# 002-0081_Rev_-.net
KiCad netlist of a schematic drawn in Altium Designer
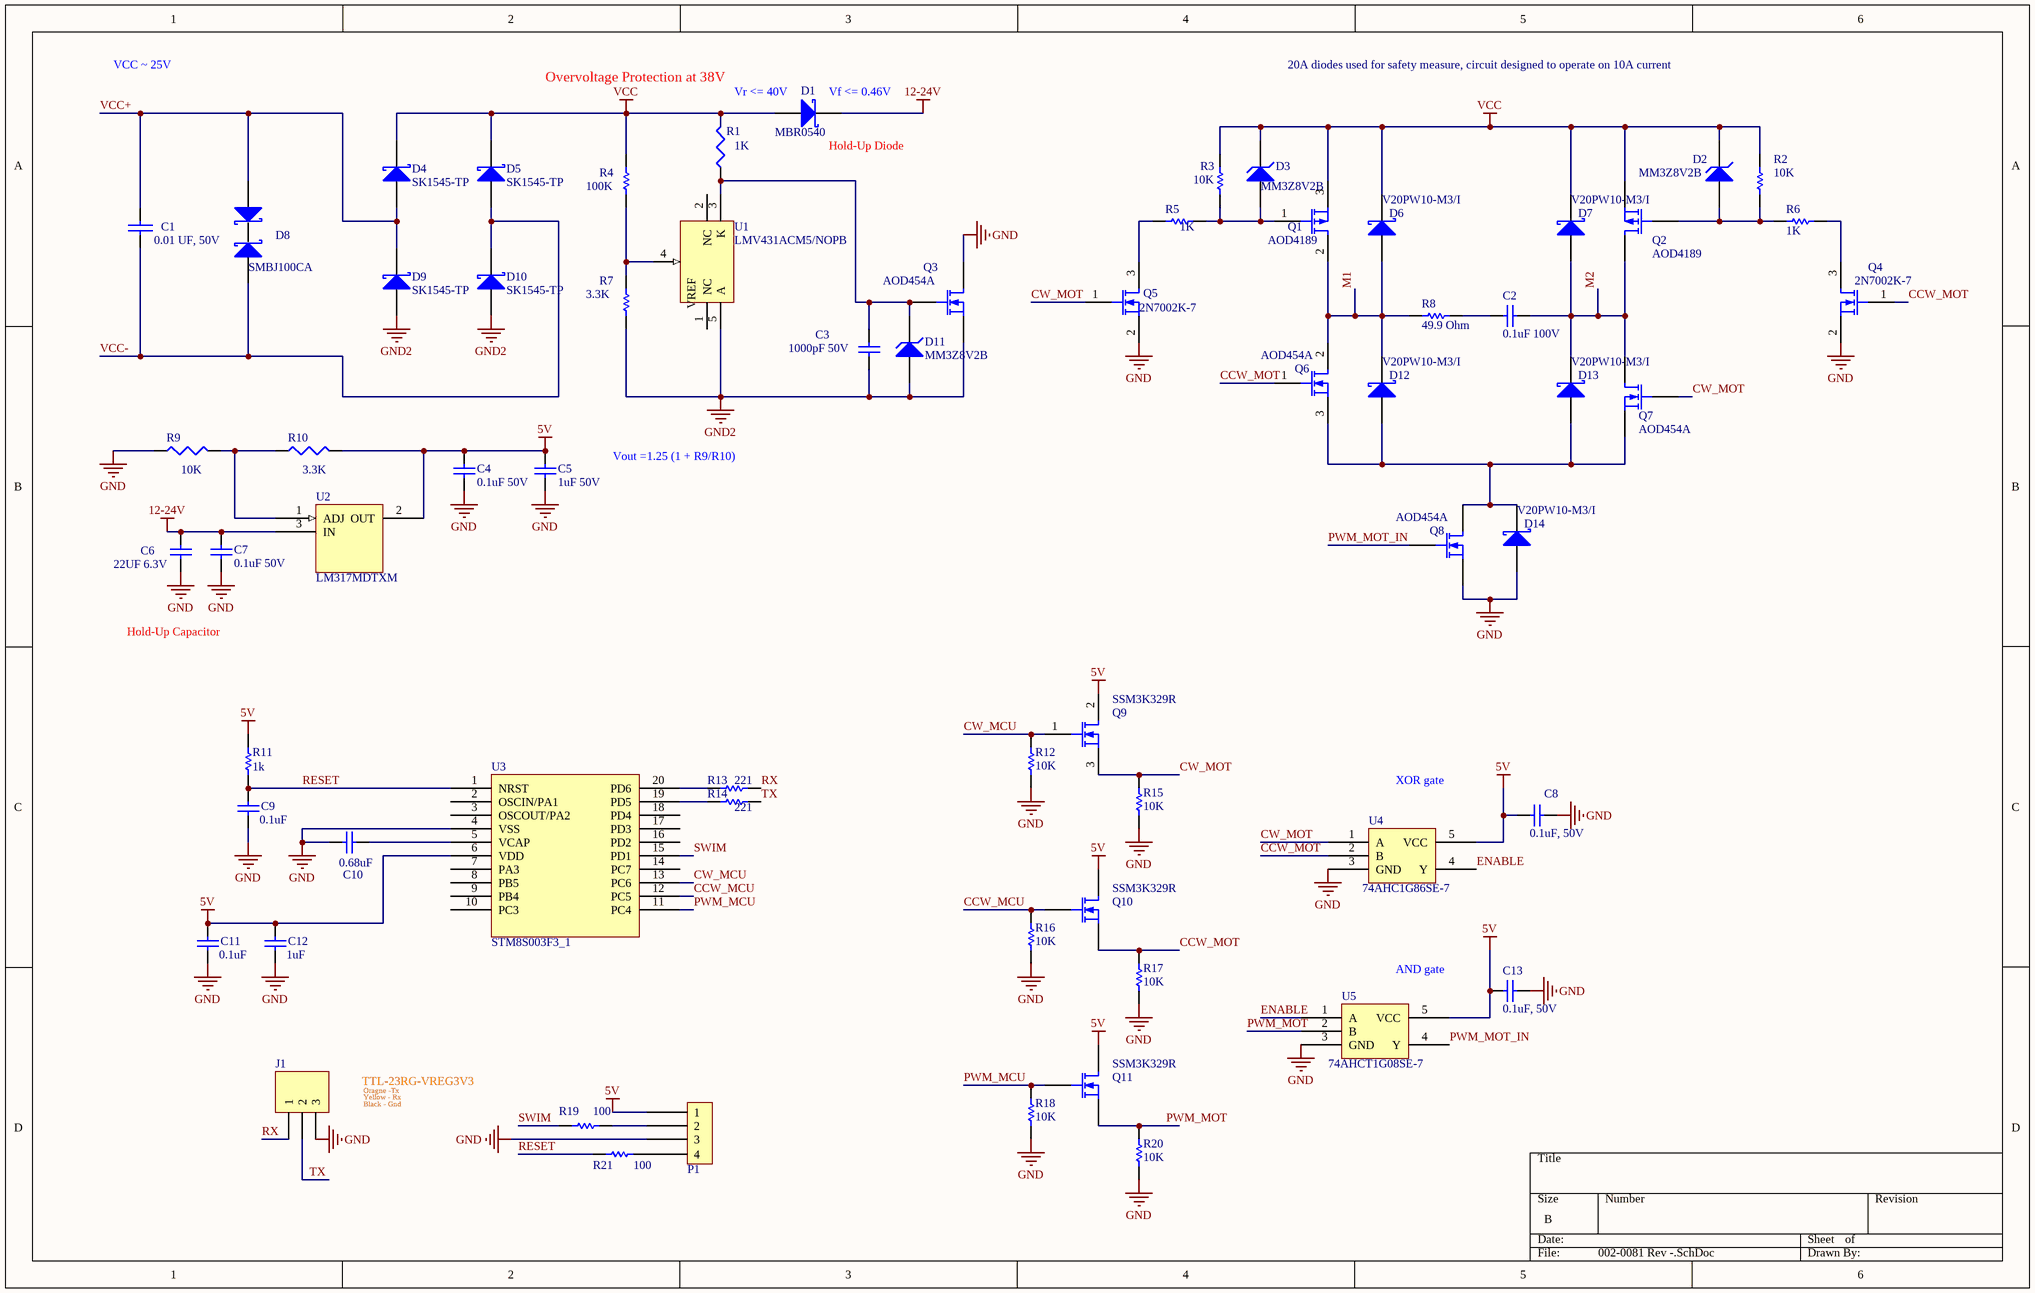
[diagram p0: 002-0081 Rev -.SchDoc]

(export (version "E")
  (design (tool "Eeschema 10.0.6"))
  (components
    (comp (ref "C1")
      (value "0.01 UF, 50V")
      (footprint "0603")
      (description "Cap Cer .01uf 50V 0603 RoHS")
      (fields
        (field (name "PEM PART NUMBER") "EE-1293")
        (field (name "MANUFACTURER") "Garrett Electronics Corporation")
      )
      (libsource (lib "*") (part "CAP"))
    )
    (comp (ref "C2")
      (value "0.1uF 100V")
      (footprint "RESC0805(2012)_N")
      (description "Cap Cer 0.1uF 100V 10% X7R 0805")
      (fields (field (name "PART NUMBER") "CL21B104KCFSFNE") (field (name "PEM PART NUMBER") "EE-1659"))
      (libsource (lib "Miscellaneous Devices") (part "Cap"))
    )
    (comp (ref "C3")
      (value "1000pF 50V")
      (footprint "0603")
      (description "CAP Cer, 0.1uF, 50V, 0603 X7R, 10%")
      (fields
        (field (name "MANUFACTURER PART NUMBER") "06035C104KAT2A")
        (field (name "PEM PART NUMBER") "EE-1343")
      )
      (libsource (lib "Miscellaneous Devices") (part "Cap"))
    )
    (comp (ref "C4")
      (value "0.1uF 50V")
      (footprint "0603")
      (description "CAP Cer, 0.1uF, 50V, 0603 X7R, 10%")
      (fields
        (field (name "MANUFACTURER PART NUMBER") "06035C104KAT2A")
        (field (name "PEM PART NUMBER") "EE-1425")
      )
      (libsource (lib "Miscellaneous Devices") (part "Cap"))
    )
    (comp (ref "C5")
      (value "1uF 50V")
      (footprint "0603")
      (description "CAP CER 1UF 50V 10% X5R 0603")
      (fields
        (field (name "MANUFACTURER PART NUMBER") "06035C104KAT2A")
        (field (name "PEM PART NUMBER") "EE-1708")
      )
      (libsource (lib "Miscellaneous Devices") (part "Cap"))
    )
    (comp (ref "C6")
      (value "22UF 6.3V")
      (footprint "0603")
      (description "CAP CER 22UF 6.3V X5R 0603")
      (fields
        (field (name "MANUFACTURER PART NUMBER") "06035C104KAT2A")
        (field (name "PEM PART NUMBER") "EE-1981")
      )
      (libsource (lib "Miscellaneous Devices") (part "Cap"))
    )
    (comp (ref "C7")
      (value "0.1uF 50V")
      (footprint "0603")
      (description "CAP Cer, 0.1uF, 50V, 0603 X7R, 10%")
      (fields
        (field (name "MANUFACTURER PART NUMBER") "06035C104KAT2A")
        (field (name "PEM PART NUMBER") "EE-1425")
      )
      (libsource (lib "Miscellaneous Devices") (part "Cap"))
    )
    (comp (ref "C8")
      (value "0.1uF, 50V")
      (footprint "0603")
      (description "CAP Cer, 0.1uF, 50V, 0603 X7R, 10%")
      (fields (field (name "PEM PART NUMBER") "EE-1425") (field (name "PART NUMBER") "06035C104KAT2A"))
      (libsource (lib "Miscellaneous Devices") (part "Cap"))
    )
    (comp (ref "C9")
      (value "0.1uF")
      (footprint "CAPC0402(1005)60_M")
      (description "Cap Cer 0.1uF 10V 10% X5R 0402")
      (fields (field (name "PART NUMBER") "LMK105BJ104KV-F") (field (name "PEM PART NUMBER") "EE-1661"))
      (libsource (lib "Miscellaneous Devices") (part "Cap"))
    )
    (comp (ref "C10")
      (value "0.68uF")
      (footprint "CAPC0402(1005)60_M")
      (description "Cap cer 0.68uF 6.3V 5% X6S 0402")
      (fields (field (name "PEM PART NUMBER") "EE-1673") (field (name "PART NUMBER") "CL05X684JQ5NNNC"))
      (libsource (lib "Miscellaneous Devices") (part "Cap"))
    )
    (comp (ref "C11")
      (value "0.1uF")
      (footprint "CAPC0402(1005)60_M")
      (description "Cap Cer 0.1uF 10V 10% X5R 0402")
      (fields (field (name "PART NUMBER") "LMK105BJ104KV-F") (field (name "PEM PART NUMBER") "EE-1661"))
      (libsource (lib "Miscellaneous Devices") (part "Cap"))
    )
    (comp (ref "C12")
      (value "1uF")
      (footprint "CAPC0402(1005)60_M")
      (description "Cap Cer 1uF 10V 10% X5R 0402")
      (fields (field (name "PART NUMBER") "C1005X5R1V105M050BC") (field (name "PEM PART NUMBER") "EE-1725"))
      (libsource (lib "Miscellaneous Devices") (part "Cap"))
    )
    (comp (ref "C13")
      (value "0.1uF, 50V")
      (footprint "0603")
      (description "Cap Cer 0.1uF 10V 10% X5R 0402")
      (fields (field (name "PEM PART NUMBER") "EE-1425") (field (name "PART NUMBER") "06035C104KAT2A"))
      (libsource (lib "Miscellaneous Devices") (part "Cap"))
    )
    (comp (ref "D1")
      (value "MBR0540")
      (footprint "SOD123/X.85")
      (description "Diode Schottky 40V 500ma SOD-123")
      (fields
        (field (name "MANUFACTURER PART NUMBER") "MBR0540-TP")
        (field (name "PEM PART NUMBER") "EE-1290")
      )
      (libsource (lib "") (part "D Schottky_1"))
    )
    (comp (ref "D2")
      (value "MM3Z8V2B")
      (footprint "SOD-323F")
      (description "DIODE ZENER 8.2V 200MW SOD323F")
      (fields (field (name "PEM PART NUMBER") "EE-1681"))
      (libsource (lib "Miscellaneous Devices") (part "D Zener"))
    )
    (comp (ref "D3")
      (value "MM3Z8V2B")
      (footprint "SOD-323F")
      (description "DIODE ZENER 8.2V 200MW SOD323F")
      (fields (field (name "PEM PART NUMBER") "EE-1681"))
      (libsource (lib "Miscellaneous Devices") (part "D Zener"))
    )
    (comp (ref "D4")
      (value "SK1545-TP")
      (footprint "SMC")
      (description "DIODE SCHOTTKY 45V 15A DO214AB")
      (fields (field (name "PEM PART NUMBER") "EE-2167"))
      (libsource (lib "Miscellaneous Devices") (part "D Schottky"))
    )
    (comp (ref "D5")
      (value "SK1545-TP")
      (footprint "SMC")
      (description "DIODE SCHOTTKY 45V 15A DO214AB")
      (fields (field (name "PEM PART NUMBER") "EE-2167"))
      (libsource (lib "Miscellaneous Devices") (part "D Schottky"))
    )
    (comp (ref "D6")
      (value "V20PW10-M3/I")
      (footprint "DPAK (TO-252-3)")
      (description "DIODE SCHOTTKY 100V 20A SLIMDPAK")
      (fields (field (name "PEM PART NUMBER") "EE-2166"))
      (libsource (lib "Miscellaneous Devices") (part "D Schottky"))
    )
    (comp (ref "D7")
      (value "V20PW10-M3/I")
      (footprint "DPAK (TO-252-3)")
      (description "DIODE SCHOTTKY 100V 20A SLIMDPAK")
      (fields (field (name "PEM PART NUMBER") "EE-2166"))
      (libsource (lib "Miscellaneous Devices") (part "D Schottky"))
    )
    (comp (ref "D8")
      (value "TVS DIODE 28VWM 45.4VC SMB")
      (footprint "SMB - Bidirection")
      (description "TVS DIODE 100VWM 162VC DO214AA")
      (fields
        (field (name "PART NUMBER") "SMBJ100CA")
        (field (name "MANUFACTURER") "ON Semiconductor")
        (field (name "PEM PART NUMBER") "EE-1946")
      )
      (libsource (lib "002-0017 Rev H") (part "Dual Zener"))
    )
    (comp (ref "D9")
      (value "SK1545-TP")
      (footprint "SMC")
      (description "DIODE SCHOTTKY 45V 15A DO214AB")
      (fields (field (name "PEM PART NUMBER") "EE-2167"))
      (libsource (lib "Miscellaneous Devices") (part "D Schottky"))
    )
    (comp (ref "D10")
      (value "SK1545-TP")
      (footprint "SMC")
      (description "DIODE SCHOTTKY 45V 15A DO214AB")
      (fields (field (name "PEM PART NUMBER") "EE-2167"))
      (libsource (lib "Miscellaneous Devices") (part "D Schottky"))
    )
    (comp (ref "D11")
      (value "MM3Z8V2B")
      (footprint "SOD-323F")
      (description "DIODE ZENER 8.2V 200MW SOD323F")
      (fields (field (name "PEM PART NUMBER") "EE-1681"))
      (libsource (lib "Miscellaneous Devices") (part "D Zener"))
    )
    (comp (ref "D12")
      (value "V20PW10-M3/I")
      (footprint "DPAK (TO-252-3)")
      (description "DIODE SCHOTTKY 100V 20A SLIMDPAK")
      (fields (field (name "PEM PART NUMBER") "EE-2166"))
      (libsource (lib "Miscellaneous Devices") (part "D Schottky"))
    )
    (comp (ref "D13")
      (value "V20PW10-M3/I")
      (footprint "DPAK (TO-252-3)")
      (description "DIODE SCHOTTKY 100V 20A SLIMDPAK")
      (fields (field (name "PEM PART NUMBER") "EE-2166"))
      (libsource (lib "Miscellaneous Devices") (part "D Schottky"))
    )
    (comp (ref "D14")
      (value "V20PW10-M3/I")
      (footprint "DPAK (TO-252-3)")
      (description "DIODE SCHOTTKY 100V 20A SLIMDPAK")
      (fields (field (name "PEM PART NUMBER") "EE-2166"))
      (libsource (lib "Miscellaneous Devices") (part "D Schottky"))
    )
    (comp (ref "J1")
      (value "RS232 Conn")
      (footprint "SCON3/.10")
      (description "CONN HDR VERT 3POS .100 TIN")
      (fields
        (field (name "PEM PART NUMBER") "EE-1116")
        (field (name "MANUFACTURER") "Phoenix Contact")
        (field (name "PUBLISHER") "Altium Limited")
      )
      (libsource (lib "Miscellaneous Connectors") (part "Header 3"))
    )
    (comp (ref "P1")
      (value "4 Pin Connector")
      (footprint "4 PIN IN-LINE")
      (fields
        (field (name "PEM PART NUMBER") "EE-1855")
        (field (name "PART NUMBER") "GRPB501VWVN-RC")
        (field (name "MANUFACTURER") "Sullins Connector Solutions")
      )
      (libsource (lib "002 - 0053 Rev A") (part "4 Pin Connector"))
    )
    (comp (ref "Q1")
      (value "AOD4189")
      (footprint "DPAK (TO-252-3)")
      (description "MOSFET P-CH 40V 40A TO252 DPAK")
      (fields (field (name "PEM PART NUMBER") "EE-1879"))
      (libsource (lib "") (part "MOSFET-P_1"))
    )
    (comp (ref "Q2")
      (value "AOD4189")
      (footprint "DPAK (TO-252-3)")
      (description "MOSFET P-CH 40V 40A TO252 DPAK")
      (fields (field (name "PEM PART NUMBER") "EE-1879"))
      (libsource (lib "Miscellaneous Devices") (part "MOSFET-P"))
    )
    (comp (ref "Q3")
      (value "AOD454A")
      (footprint "DPAK (TO-252-3)")
      (description "MOSFET N-CH 250V 16A D-PAK")
      (fields (field (name "PEM PART NUMBER") "EE-1898"))
      (libsource (lib "") (part "MOSFET-N_2"))
    )
    (comp (ref "Q4")
      (value "2N7002K-7")
      (footprint "SOT-23-3")
      (description "MOSFET N-CH 60V 0.38A SOT23-3")
      (fields (field (name "PEM PART NUMBER") "EE-2053"))
      (libsource (lib "") (part "MOSFET-N_1"))
    )
    (comp (ref "Q5")
      (value "2N7002K-7")
      (footprint "SOT-23-3")
      (description "MOSFET N-CH 60V 0.38A SOT23-3")
      (fields (field (name "PEM PART NUMBER") "EE-2053"))
      (libsource (lib "") (part "MOSFET-N_1"))
    )
    (comp (ref "Q6")
      (value "AOD454A")
      (footprint "DPAK (TO-252-3)")
      (description "MOSFET N-CH 40V 20A TO252")
      (fields
        (field (name "MANUFACTURER") "Alpha & Omega Semiconductor Inc.")
        (field (name "PEM PART NUMBER") "EE-1898")
      )
      (libsource (lib "Miscellaneous Devices") (part "MOSFET-N"))
    )
    (comp (ref "Q7")
      (value "AOD454A")
      (footprint "DPAK (TO-252-3)")
      (description "MOSFET N-CH 40V 20A TO252")
      (fields
        (field (name "MANUFACTURER") "Alpha & Omega Semiconductor Inc.")
        (field (name "PEM PART NUMBER") "EE-1898")
      )
      (libsource (lib "") (part "MOSFET-N_2"))
    )
    (comp (ref "Q8")
      (value "AOD454A")
      (footprint "DPAK (TO-252-3)")
      (description "MOSFET N-CH 40V 20A TO252")
      (fields
        (field (name "MANUFACTURER") "Alpha & Omega Semiconductor Inc.")
        (field (name "PEM PART NUMBER") "EE-1898")
      )
      (libsource (lib "") (part "MOSFET-N_2"))
    )
    (comp (ref "Q9")
      (value "SSM3K329R")
      (footprint "SOT-23F")
      (description "N-Channel 30V 3.5A (Ta) 1W (Ta) Surface Mount SOT-23F")
      (fields
        (field (name "MANUFACTURER") "Alpha & Omega Semiconductor Inc.")
        (field (name "PEM PART NUMBER") "EE-1830")
      )
      (libsource (lib "Miscellaneous Devices") (part "MOSFET-N"))
    )
    (comp (ref "Q10")
      (value "SSM3K329R")
      (footprint "SOT-23F")
      (description "N-Channel 30V 3.5A (Ta) 1W (Ta) Surface Mount SOT-23F")
      (fields
        (field (name "MANUFACTURER") "Alpha & Omega Semiconductor Inc.")
        (field (name "PEM PART NUMBER") "EE-1830")
      )
      (libsource (lib "") (part "MOSFET-N_2"))
    )
    (comp (ref "Q11")
      (value "SSM3K329R")
      (footprint "SOT-23F")
      (description "N-Channel 30V 3.5A (Ta) 1W (Ta) Surface Mount SOT-23F")
      (fields
        (field (name "PART NUMBER") "AOD454A")
        (field (name "MANUFACTURER") "Alpha & Omega Semiconductor Inc.")
      )
      (libsource (lib "") (part "MOSFET-N_2"))
    )
    (comp (ref "R1")
      (value "1K")
      (footprint "002-0081 Rev -:RESC0603(1608)_M")
      (description "RES SMD 1K OHM 1% 1/10W 0603")
      (fields
        (field (name "PEM PART NUMBER") "EE-2066")
        (field (name "Comment") "Res3")
        (field (name "PUBLISHER") "Altium Limited")
      )
      (libsource (lib "Miscellaneous Devices") (part "Res3"))
    )
    (comp (ref "R2")
      (value "10K")
      (footprint "RESC0603(1608)_M")
      (description "Res 10K 0603 1% 1/10W RoHS")
      (fields (field (name "PART NUMBER") "RK73H1JTTD1002F") (field (name "PEM PART NUMBER") "EE-1296"))
      (libsource (lib "Miscellaneous Devices") (part "Res1"))
    )
    (comp (ref "R3")
      (value "10K")
      (footprint "RESC0603(1608)_M")
      (description "Res 10K 0603 1% 1/10W RoHS")
      (fields (field (name "PART NUMBER") "RK73H1JTTD1002F") (field (name "PEM PART NUMBER") "EE-1296"))
      (libsource (lib "Miscellaneous Devices") (part "Res1"))
    )
    (comp (ref "R4")
      (value "100K")
      (footprint "RESC0603(1608)_M")
      (description "Res 100K 0603 1% 1/10W RoHS")
      (fields (field (name "PART NUMBER") "RK73H1JTTD1002F") (field (name "PEM PART NUMBER") "EE-1295"))
      (libsource (lib "Miscellaneous Devices") (part "Res1"))
    )
    (comp (ref "R5")
      (value "1K")
      (footprint "RESC0603(1608)_M")
      (description "Res 1.0K 0603 1% 1/10W RoHS")
      (fields
        (field (name "MANUFACTURER PART NUMBER") "CRCW06031K00FKEA")
        (field (name "PEM PART NUMBER") "EE-1297")
      )
      (libsource (lib "Miscellaneous Devices") (part "Res1"))
    )
    (comp (ref "R6")
      (value "1K")
      (footprint "RESC0603(1608)_M")
      (description "Res 1.0K 0603 1% 1/10W RoHS")
      (fields
        (field (name "MANUFACTURER PART NUMBER") "CRCW06031K00FKEA")
        (field (name "PEM PART NUMBER") "EE-1297")
      )
      (libsource (lib "Miscellaneous Devices") (part "Res1"))
    )
    (comp (ref "R7")
      (value "3.3K")
      (footprint "RESC0603(1608)_M")
      (description "RES 23.7K OHM 1/10W 1% 0603 SMD")
      (fields (field (name "PART NUMBER") "MCR03ERTF3301") (field (name "PEM PART NUMBER") "EE-1730"))
      (libsource (lib "Miscellaneous Devices") (part "Res1"))
    )
    (comp (ref "R8")
      (value "49.9 Ohm")
      (footprint "RESC0805(2012)_N")
      (description "Res 49.9R 0805 1% 1/8W")
      (fields (field (name "PEM PART NUMBER") "EE-1238") (field (name "PART NUMBER") "9C08052A49R9FKHFT"))
      (libsource (lib "Miscellaneous Devices") (part "Res1"))
    )
    (comp (ref "R9")
      (value "10K")
      (footprint "J1-0603")
      (description "Res 10K 0603 1% 1/10W RoHS")
      (fields (field (name "PEM PART NUMBER") "EE-1296") (field (name "PART NUMBER") "RK73H1JTTD1002F"))
      (libsource (lib "Miscellaneous Devices") (part "Res3"))
    )
    (comp (ref "R10")
      (value "3.3K")
      (footprint "J1-0603")
      (description "Res 3.3K 0603 1% 1/8W RoHS")
      (fields (field (name "PEM PART NUMBER") "EE-1730") (field (name "PART NUMBER") "MCR03ERTF3301"))
      (libsource (lib "Miscellaneous Devices") (part "Res3"))
    )
    (comp (ref "R11")
      (value "1k")
      (footprint "RESC0402(1005)_N")
      (description "Res 1K 0402 1% 1/16W RoHS")
      (fields (field (name "PEM PART NUMBER") "EE-1581") (field (name "PART NUMBER") "CRCW04021K00FKED"))
      (libsource (lib "Miscellaneous Devices") (part "Res1"))
    )
    (comp (ref "R12")
      (value "10K")
      (footprint "RESC0603(1608)_M")
      (description "Res 10K 0603 1% 1/10W RoHS")
      (fields (field (name "PART NUMBER") "RK73H1JTTD1002F") (field (name "PEM PART NUMBER") "EE-1296"))
      (libsource (lib "Miscellaneous Devices") (part "Res1"))
    )
    (comp (ref "R13")
      (value "221")
      (footprint "RESC0402(1005)_N")
      (description "RES SMD 221 OHM 1% 1/16W 0402")
      (fields (field (name "PART NUMBER") "RC1005F2210CS") (field (name "PEM PART NUMBER") "EE-1798"))
      (libsource (lib "Miscellaneous Devices") (part "Res1"))
    )
    (comp (ref "R14")
      (value "221")
      (footprint "RESC0402(1005)_N")
      (description "Res 1K 0603 1% 1/10W RoHS")
      (fields (field (name "PART NUMBER") "RC1005F2210CS") (field (name "PEM PART NUMBER") "EE-1798"))
      (libsource (lib "Miscellaneous Devices") (part "Res1"))
    )
    (comp (ref "R15")
      (value "10K")
      (footprint "RESC0603(1608)_M")
      (description "Res 10K 0603 1% 1/10W RoHS")
      (fields (field (name "PART NUMBER") "RK73H1JTTD1002F") (field (name "PEM PART NUMBER") "EE-1296"))
      (libsource (lib "Miscellaneous Devices") (part "Res1"))
    )
    (comp (ref "R16")
      (value "10K")
      (footprint "RESC0603(1608)_M")
      (description "Res 10K 0603 1% 1/10W RoHS")
      (fields (field (name "PART NUMBER") "RK73H1JTTD1002F") (field (name "PEM PART NUMBER") "EE-1296"))
      (libsource (lib "Miscellaneous Devices") (part "Res1"))
    )
    (comp (ref "R17")
      (value "10K")
      (footprint "RESC0603(1608)_M")
      (description "Res 10K 0603 1% 1/10W RoHS")
      (fields (field (name "PART NUMBER") "RK73H1JTTD1002F") (field (name "PEM PART NUMBER") "EE-1296"))
      (libsource (lib "Miscellaneous Devices") (part "Res1"))
    )
    (comp (ref "R18")
      (value "10K")
      (footprint "RESC0603(1608)_M")
      (description "Res 10K 0603 1% 1/10W RoHS")
      (fields (field (name "PART NUMBER") "RK73H1JTTD1002F") (field (name "PEM PART NUMBER") "EE-1296"))
      (libsource (lib "Miscellaneous Devices") (part "Res1"))
    )
    (comp (ref "R19")
      (value "100")
      (footprint "RESC0402(1005)_N")
      (description "Res 100R 0402 1% 1/16W RoHs")
      (fields (field (name "PEM PART NUMBER") "EE-1588") (field (name "PART NUMBER") "RC0402FR-07100RL"))
      (libsource (lib "Miscellaneous Devices") (part "Res1"))
    )
    (comp (ref "R20")
      (value "10K")
      (footprint "RESC0603(1608)_M")
      (description "Res 10K 0603 1% 1/10W RoHS")
      (fields (field (name "PART NUMBER") "RK73H1JTTD1002F") (field (name "PEM PART NUMBER") "EE-1296"))
      (libsource (lib "Miscellaneous Devices") (part "Res1"))
    )
    (comp (ref "R21")
      (value "100")
      (footprint "RESC0402(1005)_N")
      (description "Res 100R 0402 1% 1/16W RoHs")
      (fields (field (name "PEM PART NUMBER") "EE-1588") (field (name "PART NUMBER") "RC0402FR-07100RL"))
      (libsource (lib "Miscellaneous Devices") (part "Res1"))
    )
    (comp (ref "U1")
      (value "LMV431ACM5/NOPB")
      (footprint "DBV005")
      (description "IC VREF SHUNT ADJ SOT23-5")
      (fields (field (name "PEM PART NUMBER") "EE-1900"))
      (libsource (lib "TI Power Mgt Voltage Regulator") (part "TL431IDBVR"))
    )
    (comp (ref "U2")
      (value "LM317MDTXM")
      (footprint "DPAK (TO-252-3)")
      (description "SMT, IC, Adjust Voltage Reg, 0.5A, 3TERM, TO-252, 40V diff max")
      (fields
        (field (name "PEM PART NUMBER") "EE-1248")
        (field (name "MANUFACTURER") "Fairchild Semiconductor")
      )
      (libsource (lib "*") (part "LM317D2T(3)"))
    )
    (comp (ref "U3")
      (value "STM8S003F3_1")
      (footprint "UFQFPN20_V")
      (description "MCU 8BIT 8KB 16MHZ 20-UFQFPN")
      (fields (field (name "PEM PART NUMBER") "EE-1655") (field (name "PART NUMBER") "STM8S003F3U6TR"))
      (libsource (lib "SlowActuator") (part "STM8S003F3_1"))
    )
    (comp (ref "U4")
      (value "74AHC1G86SE-7")
      (footprint "SOT-353")
      (description "IC GATE XOR 1CH 2-INP SOT353")
      (fields (field (name "PEM PART NUMBER") "EE-2165") (field (name "MANUFACTURER") "Diodes Incorporated"))
      (libsource (lib "002-0066 Rev -") (part "NC7SZ08"))
    )
    (comp (ref "U5")
      (value "74AHCT1G08SE-7")
      (footprint "SOT-353")
      (description "IC GATE AND 1CH 2-INP SOT-353")
      (fields (field (name "PEM PART NUMBER") "EE-1801") (field (name "MANUFACTURER") "Diodes Incorporated"))
      (libsource (lib "002-0066 Rev -") (part "NC7SZ08"))
    )
  )
  (nets
    (net (code "1") (name "/CCW_MCU") (class "Default")
      (node (ref "Q10") (pin "1") (pinfunction "G_1") (pintype "passive"))
      (node (ref "R16") (pin "1") (pinfunction "1_1") (pintype "passive"))
      (node (ref "U3") (pin "12") (pinfunction "PC5_12") (pintype "passive"))
    )
    (net (code "2") (name "/CCW_MOT") (class "Default")
      (node (ref "Q10") (pin "3") (pinfunction "S_3") (pintype "passive"))
      (node (ref "Q4") (pin "1") (pinfunction "G_1") (pintype "passive"))
      (node (ref "Q6") (pin "1") (pinfunction "G_1") (pintype "passive"))
      (node (ref "R17") (pin "1") (pinfunction "1_1") (pintype "passive"))
      (node (ref "U4") (pin "2") (pinfunction "B_2") (pintype "passive"))
    )
    (net (code "3") (name "/CW_MCU") (class "Default")
      (node (ref "Q9") (pin "1") (pinfunction "G_1") (pintype "passive"))
      (node (ref "R12") (pin "1") (pinfunction "1_1") (pintype "passive"))
      (node (ref "U3") (pin "13") (pinfunction "PC6_13") (pintype "passive"))
    )
    (net (code "4") (name "/CW_MOT") (class "Default")
      (node (ref "Q5") (pin "1") (pinfunction "G_1") (pintype "passive"))
      (node (ref "Q7") (pin "1") (pinfunction "G_1") (pintype "passive"))
      (node (ref "Q9") (pin "3") (pinfunction "S_3") (pintype "passive"))
      (node (ref "R15") (pin "1") (pinfunction "1_1") (pintype "passive"))
      (node (ref "U4") (pin "1") (pinfunction "A_1") (pintype "passive"))
    )
    (net (code "5") (name "/ENABLE") (class "Default")
      (node (ref "U4") (pin "4") (pinfunction "Y_4") (pintype "passive"))
      (node (ref "U5") (pin "1") (pinfunction "A_1") (pintype "passive"))
    )
    (net (code "6") (name "/M1") (class "Default")
      (node (ref "D12") (pin "2") (pinfunction "K_2") (pintype "passive"))
      (node (ref "D6") (pin "1") (pinfunction "A_1") (pintype "passive"))
      (node (ref "Q1") (pin "2") (pinfunction "D_2") (pintype "passive"))
      (node (ref "Q6") (pin "2") (pinfunction "D_2") (pintype "passive"))
      (node (ref "R8") (pin "2") (pinfunction "2_2") (pintype "passive"))
    )
    (net (code "7") (name "/M2") (class "Default")
      (node (ref "C2") (pin "1") (pinfunction "1_1") (pintype "passive"))
      (node (ref "D13") (pin "2") (pinfunction "K_2") (pintype "passive"))
      (node (ref "D7") (pin "1") (pinfunction "A_1") (pintype "passive"))
      (node (ref "Q2") (pin "2") (pinfunction "D_2") (pintype "passive"))
      (node (ref "Q7") (pin "2") (pinfunction "D_2") (pintype "passive"))
    )
    (net (code "8") (name "/PWM_MCU") (class "Default")
      (node (ref "Q11") (pin "1") (pinfunction "G_1") (pintype "passive"))
      (node (ref "R18") (pin "1") (pinfunction "1_1") (pintype "passive"))
      (node (ref "U3") (pin "11") (pinfunction "PC4_11") (pintype "passive"))
    )
    (net (code "9") (name "/PWM_MOT") (class "Default")
      (node (ref "Q11") (pin "3") (pinfunction "S_3") (pintype "passive"))
      (node (ref "R20") (pin "1") (pinfunction "1_1") (pintype "passive"))
      (node (ref "U5") (pin "2") (pinfunction "B_2") (pintype "passive"))
    )
    (net (code "10") (name "/PWM_MOT_IN") (class "Default")
      (node (ref "Q8") (pin "1") (pinfunction "G_1") (pintype "passive"))
      (node (ref "U5") (pin "4") (pinfunction "Y_4") (pintype "passive"))
    )
    (net (code "11") (name "/RESET") (class "Default")
      (node (ref "C9") (pin "2") (pinfunction "2_2") (pintype "passive"))
      (node (ref "R11") (pin "1") (pinfunction "1_1") (pintype "passive"))
      (node (ref "R21") (pin "1") (pinfunction "1_1") (pintype "passive"))
      (node (ref "U3") (pin "1") (pinfunction "NRST_1") (pintype "passive"))
    )
    (net (code "12") (name "/RX") (class "Default")
      (node (ref "J1") (pin "1") (pinfunction "1_1") (pintype "passive"))
      (node (ref "R13") (pin "2") (pinfunction "2_2") (pintype "passive"))
    )
    (net (code "13") (name "/SWIM") (class "Default")
      (node (ref "R19") (pin "1") (pinfunction "1_1") (pintype "passive"))
      (node (ref "U3") (pin "15") (pinfunction "PD1_15") (pintype "passive"))
    )
    (net (code "14") (name "/TX") (class "Default")
      (node (ref "J1") (pin "2") (pinfunction "2_2") (pintype "passive"))
      (node (ref "R14") (pin "2") (pinfunction "2_2") (pintype "passive"))
    )
    (net (code "15") (name "/VCC+") (class "Default")
      (node (ref "C1") (pin "1") (pinfunction "1_1") (pintype "passive"))
      (node (ref "D4") (pin "1") (pinfunction "A_1") (pintype "passive"))
      (node (ref "D8") (pin "2") (pinfunction "2_2") (pintype "passive"))
      (node (ref "D9") (pin "2") (pinfunction "K_2") (pintype "passive"))
    )
    (net (code "16") (name "/VCC-") (class "Default")
      (node (ref "C1") (pin "2") (pinfunction "2_2") (pintype "passive"))
      (node (ref "D10") (pin "2") (pinfunction "K_2") (pintype "passive"))
      (node (ref "D5") (pin "1") (pinfunction "A_1") (pintype "passive"))
      (node (ref "D8") (pin "1") (pinfunction "1_1") (pintype "passive"))
    )
    (net (code "17") (name "5V") (class "Default")
      (node (ref "C11") (pin "2") (pinfunction "2_2") (pintype "passive"))
      (node (ref "C12") (pin "2") (pinfunction "2_2") (pintype "passive"))
      (node (ref "C13") (pin "2") (pinfunction "2_2") (pintype "passive"))
      (node (ref "C4") (pin "2") (pinfunction "2_2") (pintype "passive"))
      (node (ref "C5") (pin "2") (pinfunction "2_2") (pintype "passive"))
      (node (ref "C8") (pin "2") (pinfunction "2_2") (pintype "passive"))
      (node (ref "P1") (pin "1") (pinfunction "1_1") (pintype "passive"))
      (node (ref "Q10") (pin "2") (pinfunction "D_2") (pintype "passive"))
      (node (ref "Q11") (pin "2") (pinfunction "D_2") (pintype "passive"))
      (node (ref "Q9") (pin "2") (pinfunction "D_2") (pintype "passive"))
      (node (ref "R10") (pin "2") (pinfunction "2_2") (pintype "passive"))
      (node (ref "R11") (pin "2") (pinfunction "2_2") (pintype "passive"))
      (node (ref "U2") (pin "2") (pinfunction "OUT_2") (pintype "power_in"))
      (node (ref "U3") (pin "6") (pinfunction "VDD_6") (pintype "passive"))
      (node (ref "U4") (pin "5") (pinfunction "VCC_5") (pintype "passive"))
      (node (ref "U5") (pin "5") (pinfunction "VCC_5") (pintype "passive"))
    )
    (net (code "18") (name "12-24V") (class "Default")
      (node (ref "C6") (pin "2") (pinfunction "2_2") (pintype "passive"))
      (node (ref "C7") (pin "2") (pinfunction "2_2") (pintype "passive"))
      (node (ref "D1") (pin "1") (pinfunction "K_1") (pintype "passive"))
      (node (ref "U2") (pin "3") (pinfunction "IN_3") (pintype "power_in"))
    )
    (net (code "19") (name "GND") (class "Default")
      (node (ref "C10") (pin "1") (pinfunction "1_1") (pintype "passive"))
      (node (ref "C11") (pin "1") (pinfunction "1_1") (pintype "passive"))
      (node (ref "C12") (pin "1") (pinfunction "1_1") (pintype "passive"))
      (node (ref "C13") (pin "1") (pinfunction "1_1") (pintype "passive"))
      (node (ref "C4") (pin "1") (pinfunction "1_1") (pintype "passive"))
      (node (ref "C5") (pin "1") (pinfunction "1_1") (pintype "passive"))
      (node (ref "C6") (pin "1") (pinfunction "1_1") (pintype "passive"))
      (node (ref "C7") (pin "1") (pinfunction "1_1") (pintype "passive"))
      (node (ref "C8") (pin "1") (pinfunction "1_1") (pintype "passive"))
      (node (ref "C9") (pin "1") (pinfunction "1_1") (pintype "passive"))
      (node (ref "D14") (pin "1") (pinfunction "A_1") (pintype "passive"))
      (node (ref "J1") (pin "3") (pinfunction "3_3") (pintype "passive"))
      (node (ref "P1") (pin "3") (pinfunction "3_3") (pintype "passive"))
      (node (ref "Q3") (pin "2") (pinfunction "D_2") (pintype "passive"))
      (node (ref "Q4") (pin "2") (pinfunction "S_2") (pintype "passive"))
      (node (ref "Q5") (pin "2") (pinfunction "S_2") (pintype "passive"))
      (node (ref "Q8") (pin "3") (pinfunction "S_3") (pintype "passive"))
      (node (ref "R12") (pin "2") (pinfunction "2_2") (pintype "passive"))
      (node (ref "R15") (pin "2") (pinfunction "2_2") (pintype "passive"))
      (node (ref "R16") (pin "2") (pinfunction "2_2") (pintype "passive"))
      (node (ref "R17") (pin "2") (pinfunction "2_2") (pintype "passive"))
      (node (ref "R18") (pin "2") (pinfunction "2_2") (pintype "passive"))
      (node (ref "R20") (pin "2") (pinfunction "2_2") (pintype "passive"))
      (node (ref "R9") (pin "1") (pinfunction "1_1") (pintype "passive"))
      (node (ref "U3") (pin "4") (pinfunction "VSS_4") (pintype "passive"))
      (node (ref "U4") (pin "3") (pinfunction "GND_3") (pintype "passive"))
      (node (ref "U5") (pin "3") (pinfunction "GND_3") (pintype "passive"))
    )
    (net (code "20") (name "GND2") (class "Default")
      (node (ref "C3") (pin "1") (pinfunction "1_1") (pintype "passive"))
      (node (ref "D10") (pin "1") (pinfunction "A_1") (pintype "passive"))
      (node (ref "D11") (pin "1") (pinfunction "A_1") (pintype "passive"))
      (node (ref "D9") (pin "1") (pinfunction "A_1") (pintype "passive"))
      (node (ref "Q3") (pin "3") (pinfunction "S_3") (pintype "passive"))
      (node (ref "R7") (pin "2") (pinfunction "2_2") (pintype "passive"))
      (node (ref "U1") (pin "5") (pinfunction "A_5") (pintype "power_in"))
    )
    (net (code "21") (name "Net-(C2-Pad2)") (class "Default")
      (node (ref "C2") (pin "2") (pinfunction "2_2") (pintype "passive"))
      (node (ref "R8") (pin "1") (pinfunction "1_1") (pintype "passive"))
    )
    (net (code "22") (name "Net-(D2-A)") (class "Default")
      (node (ref "D2") (pin "1") (pinfunction "A_1") (pintype "passive"))
      (node (ref "Q2") (pin "1") (pinfunction "G_1") (pintype "passive"))
      (node (ref "R2") (pin "2") (pinfunction "2_2") (pintype "passive"))
      (node (ref "R6") (pin "1") (pinfunction "1_1") (pintype "passive"))
    )
    (net (code "23") (name "Net-(D3-A)") (class "Default")
      (node (ref "D3") (pin "1") (pinfunction "A_1") (pintype "passive"))
      (node (ref "Q1") (pin "1") (pinfunction "G_1") (pintype "passive"))
      (node (ref "R3") (pin "2") (pinfunction "2_2") (pintype "passive"))
      (node (ref "R5") (pin "2") (pinfunction "2_2") (pintype "passive"))
    )
    (net (code "24") (name "Net-(D11-K)") (class "Default")
      (node (ref "C3") (pin "2") (pinfunction "2_2") (pintype "passive"))
      (node (ref "D11") (pin "2") (pinfunction "K_2") (pintype "passive"))
      (node (ref "Q3") (pin "1") (pinfunction "G_1") (pintype "passive"))
      (node (ref "R1") (pin "1") (pinfunction "1_1") (pintype "passive"))
      (node (ref "U1") (pin "3") (pinfunction "K_3") (pintype "power_in"))
    )
    (net (code "25") (name "Net-(D12-A)") (class "Default")
      (node (ref "D12") (pin "1") (pinfunction "A_1") (pintype "passive"))
      (node (ref "D13") (pin "1") (pinfunction "A_1") (pintype "passive"))
      (node (ref "D14") (pin "2") (pinfunction "K_2") (pintype "passive"))
      (node (ref "Q6") (pin "3") (pinfunction "S_3") (pintype "passive"))
      (node (ref "Q7") (pin "3") (pinfunction "S_3") (pintype "passive"))
      (node (ref "Q8") (pin "2") (pinfunction "D_2") (pintype "passive"))
    )
    (net (code "26") (name "Net-(P1-Pad2)") (class "Default")
      (node (ref "P1") (pin "2") (pinfunction "2_2") (pintype "passive"))
      (node (ref "R19") (pin "2") (pinfunction "2_2") (pintype "passive"))
    )
    (net (code "27") (name "Net-(P1-Pad4)") (class "Default")
      (node (ref "P1") (pin "4") (pinfunction "4_4") (pintype "passive"))
      (node (ref "R21") (pin "2") (pinfunction "2_2") (pintype "passive"))
    )
    (net (code "28") (name "Net-(Q4-D)") (class "Default")
      (node (ref "Q4") (pin "3") (pinfunction "D_3") (pintype "passive"))
      (node (ref "R6") (pin "2") (pinfunction "2_2") (pintype "passive"))
    )
    (net (code "29") (name "Net-(Q5-D)") (class "Default")
      (node (ref "Q5") (pin "3") (pinfunction "D_3") (pintype "passive"))
      (node (ref "R5") (pin "1") (pinfunction "1_1") (pintype "passive"))
    )
    (net (code "30") (name "Net-(U1-REF)") (class "Default")
      (node (ref "R4") (pin "2") (pinfunction "2_2") (pintype "passive"))
      (node (ref "R7") (pin "1") (pinfunction "1_1") (pintype "passive"))
      (node (ref "U1") (pin "4") (pinfunction "REF_4") (pintype "input"))
    )
    (net (code "31") (name "Net-(U2-ADJ)") (class "Default")
      (node (ref "R10") (pin "1") (pinfunction "1_1") (pintype "passive"))
      (node (ref "R9") (pin "2") (pinfunction "2_2") (pintype "passive"))
      (node (ref "U2") (pin "1") (pinfunction "ADJ_1") (pintype "input"))
    )
    (net (code "32") (name "Net-(U3-PD5)") (class "Default")
      (node (ref "R14") (pin "1") (pinfunction "1_1") (pintype "passive"))
      (node (ref "U3") (pin "19") (pinfunction "PD5_19") (pintype "passive"))
    )
    (net (code "33") (name "Net-(U3-PD6)") (class "Default")
      (node (ref "R13") (pin "1") (pinfunction "1_1") (pintype "passive"))
      (node (ref "U3") (pin "20") (pinfunction "PD6_20") (pintype "passive"))
    )
    (net (code "34") (name "Net-(U3-VCAP)") (class "Default")
      (node (ref "C10") (pin "2") (pinfunction "2_2") (pintype "passive"))
      (node (ref "U3") (pin "5") (pinfunction "VCAP_5") (pintype "passive"))
    )
    (net (code "35") (name "VCC") (class "Default")
      (node (ref "D1") (pin "2") (pinfunction "A_2") (pintype "passive"))
      (node (ref "D2") (pin "2") (pinfunction "K_2") (pintype "passive"))
      (node (ref "D3") (pin "2") (pinfunction "K_2") (pintype "passive"))
      (node (ref "D4") (pin "2") (pinfunction "K_2") (pintype "passive"))
      (node (ref "D5") (pin "2") (pinfunction "K_2") (pintype "passive"))
      (node (ref "D6") (pin "2") (pinfunction "K_2") (pintype "passive"))
      (node (ref "D7") (pin "2") (pinfunction "K_2") (pintype "passive"))
      (node (ref "Q1") (pin "3") (pinfunction "S_3") (pintype "passive"))
      (node (ref "Q2") (pin "3") (pinfunction "S_3") (pintype "passive"))
      (node (ref "R1") (pin "2") (pinfunction "2_2") (pintype "passive"))
      (node (ref "R2") (pin "1") (pinfunction "1_1") (pintype "passive"))
      (node (ref "R3") (pin "1") (pinfunction "1_1") (pintype "passive"))
      (node (ref "R4") (pin "1") (pinfunction "1_1") (pintype "passive"))
    )
    (net (code "36") (name "unconnected-(U1-NC-Pad1)") (class "Default")
      (node (ref "U1") (pin "1") (pinfunction "NC_1") (pintype "passive"))
    )
    (net (code "37") (name "unconnected-(U1-NC-Pad2)") (class "Default")
      (node (ref "U1") (pin "2") (pinfunction "NC_2") (pintype "passive"))
    )
    (net (code "38") (name "unconnected-(U3-OSCIN{slash}PA1-Pad2)") (class "Default")
      (node (ref "U3") (pin "2") (pinfunction "OSCIN/PA1_2") (pintype "passive"))
    )
    (net (code "39") (name "unconnected-(U3-OSCOUT{slash}PA2-Pad3)") (class "Default")
      (node (ref "U3") (pin "3") (pinfunction "OSCOUT/PA2_3") (pintype "passive"))
    )
    (net (code "40") (name "unconnected-(U3-PA3-Pad7)") (class "Default")
      (node (ref "U3") (pin "7") (pinfunction "PA3_7") (pintype "passive"))
    )
    (net (code "41") (name "unconnected-(U3-PB4-Pad9)") (class "Default")
      (node (ref "U3") (pin "9") (pinfunction "PB4_9") (pintype "passive"))
    )
    (net (code "42") (name "unconnected-(U3-PB5-Pad8)") (class "Default")
      (node (ref "U3") (pin "8") (pinfunction "PB5_8") (pintype "passive"))
    )
    (net (code "43") (name "unconnected-(U3-PC3-Pad10)") (class "Default")
      (node (ref "U3") (pin "10") (pinfunction "PC3_10") (pintype "passive"))
    )
    (net (code "44") (name "unconnected-(U3-PC7-Pad14)") (class "Default")
      (node (ref "U3") (pin "14") (pinfunction "PC7_14") (pintype "passive"))
    )
    (net (code "45") (name "unconnected-(U3-PD2-Pad16)") (class "Default")
      (node (ref "U3") (pin "16") (pinfunction "PD2_16") (pintype "passive"))
    )
    (net (code "46") (name "unconnected-(U3-PD3-Pad17)") (class "Default")
      (node (ref "U3") (pin "17") (pinfunction "PD3_17") (pintype "passive"))
    )
    (net (code "47") (name "unconnected-(U3-PD4-Pad18)") (class "Default")
      (node (ref "U3") (pin "18") (pinfunction "PD4_18") (pintype "passive"))
    )
  )
)
